# 3_Sensors.net
KiCad netlist of a schematic drawn in Altium Designer
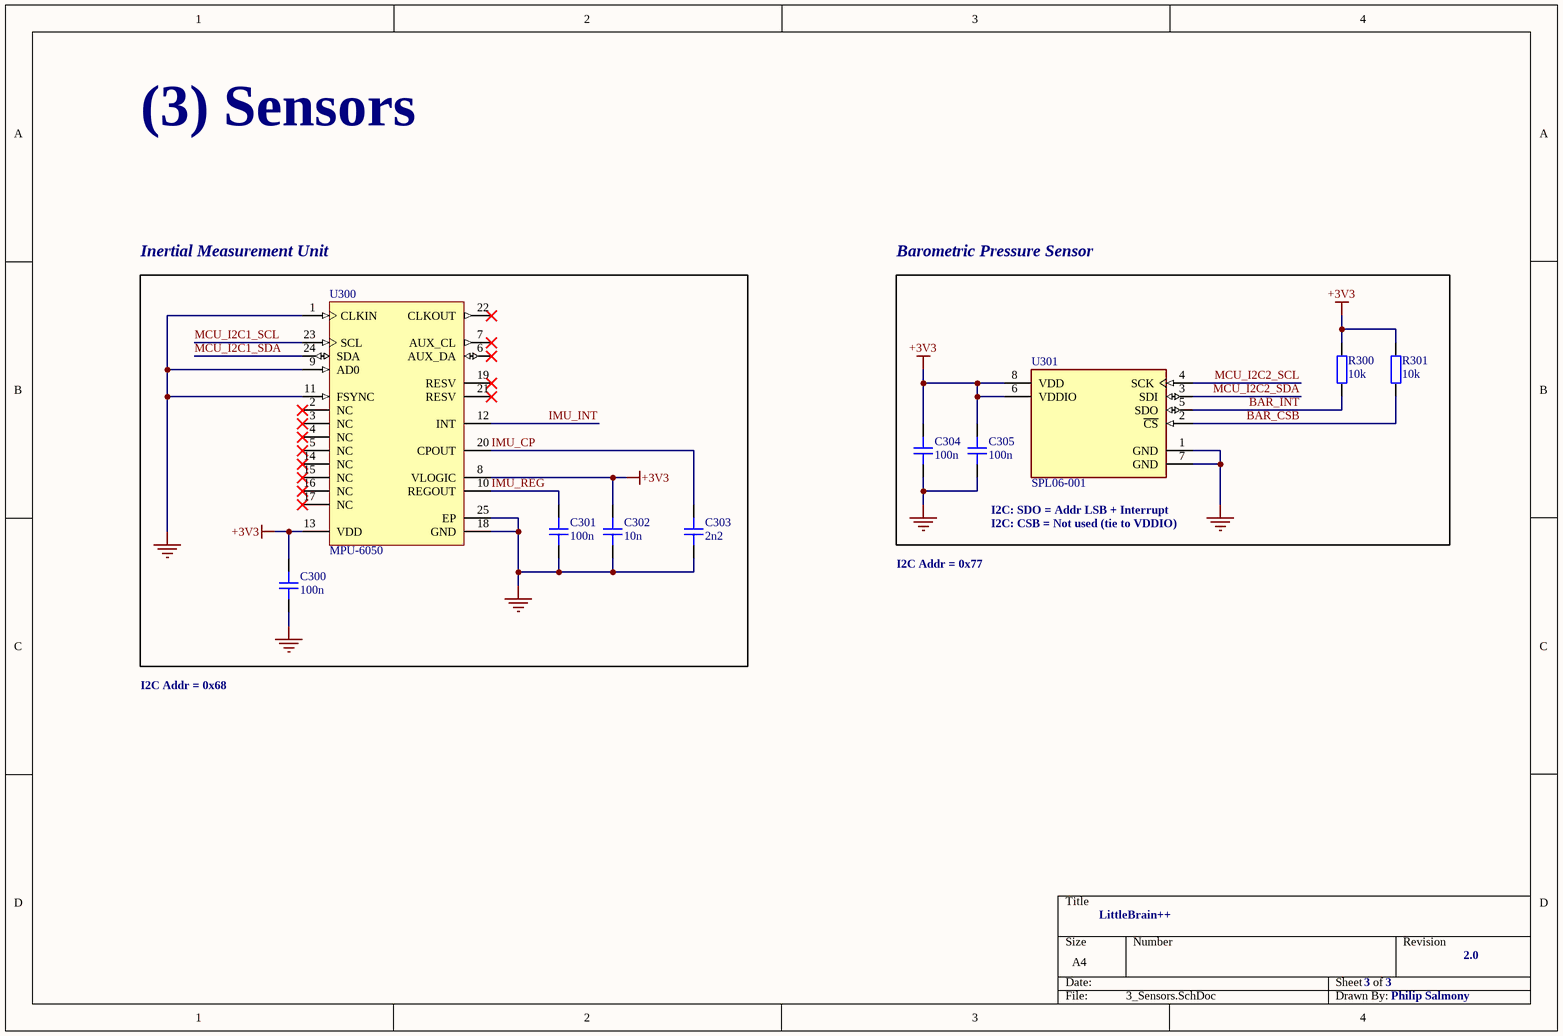
[diagram p0: 3_Sensors.SchDoc]

(export (version "E")
  (design (tool "Eeschema 10.0.6"))
  (components
    (comp (ref "C300")
      (value "100n")
      (footprint "CAP_0402")
      (description "Capacitor SMD 0402 16V")
      (libsource (lib "Schematic-Lib-PhilsLab") (part "CAP_0402_16V"))
    )
    (comp (ref "C301")
      (value "100n")
      (footprint "CAP_0402")
      (description "Capacitor SMD 0402 16V")
      (libsource (lib "Schematic-Lib-PhilsLab") (part "CAP_0402_16V"))
    )
    (comp (ref "C302")
      (value "10n")
      (footprint "CAP_0402")
      (description "Capacitor SMD 0402 16V")
      (libsource (lib "Schematic-Lib-PhilsLab") (part "CAP_0402_16V"))
    )
    (comp (ref "C303")
      (value "2n2")
      (footprint "CAP_0402")
      (description "Capacitor SMD 0402 16V")
      (libsource (lib "Schematic-Lib-PhilsLab") (part "CAP_0402_16V"))
    )
    (comp (ref "C304")
      (value "100n")
      (footprint "CAP_0402")
      (description "Capacitor SMD 0402 16V")
      (libsource (lib "Schematic-Lib-PhilsLab") (part "CAP_0402_16V"))
    )
    (comp (ref "C305")
      (value "100n")
      (footprint "CAP_0402")
      (description "Capacitor SMD 0402 16V")
      (libsource (lib "Schematic-Lib-PhilsLab") (part "CAP_0402_16V"))
    )
    (comp (ref "R300")
      (value "10k")
      (footprint "RES_0402")
      (description "Resistor SMD 0402")
      (libsource (lib "Schematic-Lib-PhilsLab") (part "RES_0402"))
    )
    (comp (ref "R301")
      (value "10k")
      (footprint "RES_0402")
      (description "Resistor SMD 0402")
      (libsource (lib "Schematic-Lib-PhilsLab") (part "RES_0402"))
    )
    (comp (ref "U300")
      (value "MPU-6050")
      (footprint "IS-QFN-24_V")
      (fields (field (name "MANUFACTURER") "InvenSense"))
      (libsource (lib "Altium Content Vault") (part "IS-MPU-6050-QFN-24"))
    )
    (comp (ref "U301")
      (value "SPL06-001")
      (footprint "FP-BMP280-MFG")
      (description "SENSOR PRESSURE ABS")
      (libsource (lib "Altium Content Vault") (part "69b1aacbb03d82763a43fac02afba64"))
    )
  )
  (nets
    (net (code "1") (name "+3V3") (class "Default")
      (node (ref "C300") (pin "2") (pinfunction "2_2") (pintype "passive"))
      (node (ref "C302") (pin "2") (pinfunction "2_2") (pintype "passive"))
      (node (ref "C304") (pin "2") (pinfunction "2_2") (pintype "passive"))
      (node (ref "C305") (pin "2") (pinfunction "2_2") (pintype "passive"))
      (node (ref "R300") (pin "2") (pinfunction "2_2") (pintype "passive"))
      (node (ref "R301") (pin "2") (pinfunction "2_2") (pintype "passive"))
      (node (ref "U300") (pin "13") (pinfunction "VDD_13") (pintype "power_in"))
      (node (ref "U300") (pin "8") (pinfunction "VLOGIC_8") (pintype "power_in"))
      (node (ref "U301") (pin "6") (pinfunction "VDDIO_6") (pintype "power_in"))
      (node (ref "U301") (pin "8") (pinfunction "VDD_8") (pintype "power_in"))
    )
    (net (code "2") (name "/BAR_CSB") (class "Default")
      (node (ref "R301") (pin "1") (pinfunction "1_1") (pintype "passive"))
      (node (ref "U301") (pin "2") (pinfunction "~{CS}_2") (pintype "input"))
    )
    (net (code "3") (name "/BAR_INT") (class "Default")
      (node (ref "R300") (pin "1") (pinfunction "1_1") (pintype "passive"))
      (node (ref "U301") (pin "5") (pinfunction "SDO_5") (pintype "bidirectional"))
    )
    (net (code "4") (name "/IMU_CP") (class "Default")
      (node (ref "C303") (pin "2") (pinfunction "2_2") (pintype "passive"))
      (node (ref "U300") (pin "20") (pinfunction "CPOUT_20") (pintype "passive"))
    )
    (net (code "5") (name "/IMU_INT") (class "Default")
      (node (ref "U300") (pin "12") (pinfunction "INT_12") (pintype "open_collector"))
    )
    (net (code "6") (name "/IMU_REG") (class "Default")
      (node (ref "C301") (pin "2") (pinfunction "2_2") (pintype "passive"))
      (node (ref "U300") (pin "10") (pinfunction "REGOUT_10") (pintype "passive"))
    )
    (net (code "7") (name "/MCU_I2C1_SCL") (class "Default")
      (node (ref "U300") (pin "23") (pinfunction "SCL_23") (pintype "input"))
    )
    (net (code "8") (name "/MCU_I2C1_SDA") (class "Default")
      (node (ref "U300") (pin "24") (pinfunction "SDA_24") (pintype "bidirectional"))
    )
    (net (code "9") (name "/MCU_I2C2_SCL") (class "Default")
      (node (ref "U301") (pin "4") (pinfunction "SCK_4") (pintype "input"))
    )
    (net (code "10") (name "/MCU_I2C2_SDA") (class "Default")
      (node (ref "U301") (pin "3") (pinfunction "SDI_3") (pintype "bidirectional"))
    )
    (net (code "11") (name "GND") (class "Default")
      (node (ref "C300") (pin "1") (pinfunction "1_1") (pintype "passive"))
      (node (ref "C301") (pin "1") (pinfunction "1_1") (pintype "passive"))
      (node (ref "C302") (pin "1") (pinfunction "1_1") (pintype "passive"))
      (node (ref "C303") (pin "1") (pinfunction "1_1") (pintype "passive"))
      (node (ref "C304") (pin "1") (pinfunction "1_1") (pintype "passive"))
      (node (ref "C305") (pin "1") (pinfunction "1_1") (pintype "passive"))
      (node (ref "U300") (pin "1") (pinfunction "CLKIN_1") (pintype "input"))
      (node (ref "U300") (pin "11") (pinfunction "FSYNC_11") (pintype "input"))
      (node (ref "U300") (pin "18") (pinfunction "GND_18") (pintype "power_in"))
      (node (ref "U300") (pin "25") (pinfunction "EP_25") (pintype "power_in"))
      (node (ref "U300") (pin "9") (pinfunction "AD0_9") (pintype "input"))
      (node (ref "U301") (pin "1") (pinfunction "GND_1") (pintype "power_in"))
      (node (ref "U301") (pin "7") (pinfunction "GND_7") (pintype "power_in"))
    )
    (net (code "12") (name "unconnected-(U300-AUX_CL-Pad7)") (class "Default")
      (node (ref "U300") (pin "7") (pinfunction "AUX_CL_7") (pintype "output+no_connect"))
    )
    (net (code "13") (name "unconnected-(U300-AUX_DA-Pad6)") (class "Default")
      (node (ref "U300") (pin "6") (pinfunction "AUX_DA_6") (pintype "bidirectional+no_connect"))
    )
    (net (code "14") (name "unconnected-(U300-CLKOUT-Pad22)") (class "Default")
      (node (ref "U300") (pin "22") (pinfunction "CLKOUT_22") (pintype "output+no_connect"))
    )
    (net (code "15") (name "unconnected-(U300-NC-Pad2)") (class "Default")
      (node (ref "U300") (pin "2") (pinfunction "NC_2") (pintype "passive+no_connect"))
    )
    (net (code "16") (name "unconnected-(U300-NC-Pad3)") (class "Default")
      (node (ref "U300") (pin "3") (pinfunction "NC_3") (pintype "passive+no_connect"))
    )
    (net (code "17") (name "unconnected-(U300-NC-Pad4)") (class "Default")
      (node (ref "U300") (pin "4") (pinfunction "NC_4") (pintype "passive+no_connect"))
    )
    (net (code "18") (name "unconnected-(U300-NC-Pad5)") (class "Default")
      (node (ref "U300") (pin "5") (pinfunction "NC_5") (pintype "passive+no_connect"))
    )
    (net (code "19") (name "unconnected-(U300-NC-Pad14)") (class "Default")
      (node (ref "U300") (pin "14") (pinfunction "NC_14") (pintype "passive+no_connect"))
    )
    (net (code "20") (name "unconnected-(U300-NC-Pad15)") (class "Default")
      (node (ref "U300") (pin "15") (pinfunction "NC_15") (pintype "passive+no_connect"))
    )
    (net (code "21") (name "unconnected-(U300-NC-Pad16)") (class "Default")
      (node (ref "U300") (pin "16") (pinfunction "NC_16") (pintype "passive+no_connect"))
    )
    (net (code "22") (name "unconnected-(U300-NC-Pad17)") (class "Default")
      (node (ref "U300") (pin "17") (pinfunction "NC_17") (pintype "passive+no_connect"))
    )
    (net (code "23") (name "unconnected-(U300-RESV-Pad19)") (class "Default")
      (node (ref "U300") (pin "19") (pinfunction "RESV_19") (pintype "passive+no_connect"))
    )
    (net (code "24") (name "unconnected-(U300-RESV-Pad21)") (class "Default")
      (node (ref "U300") (pin "21") (pinfunction "RESV_21") (pintype "passive+no_connect"))
    )
  )
)
